# Havashenasi.net
KiCad netlist of a schematic drawn in Altium Designer
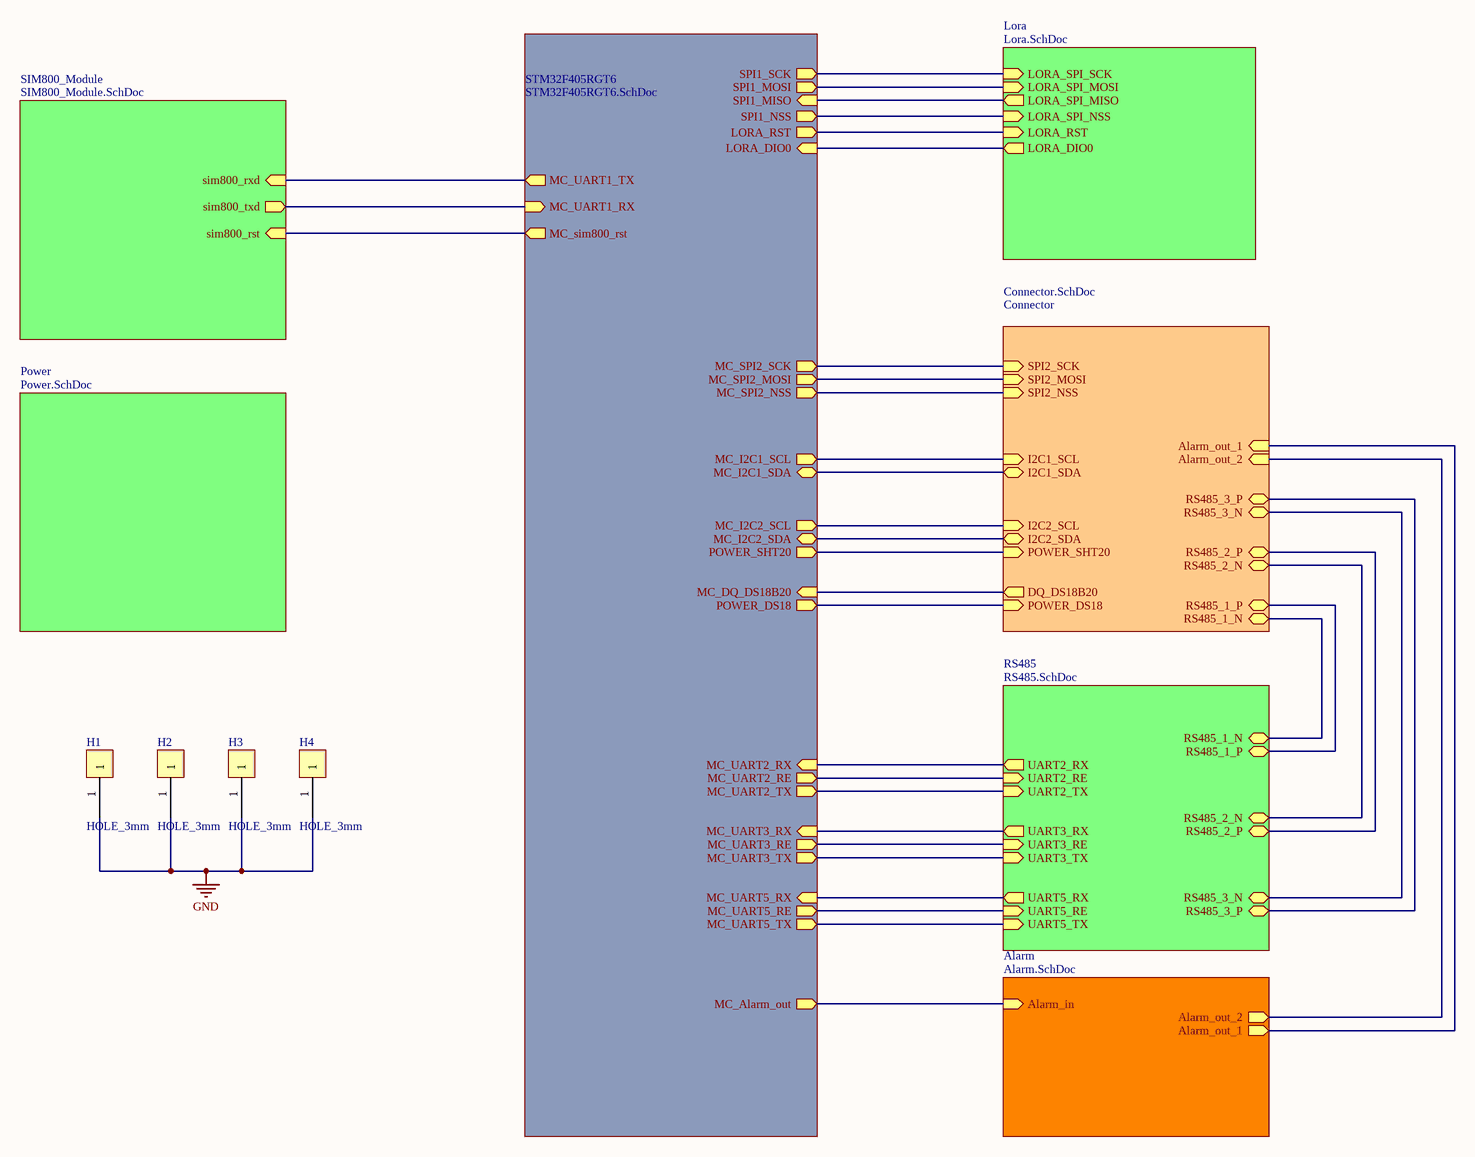
[diagram p0: Havashenasi.SchDoc]

(export (version "E")
  (design (tool "Eeschema 10.0.6"))
  (components
    (comp (ref "H1") (value "HOLE_3mm") (footprint "Hole_3mm") (libsource (lib "AfraLIB") (part "HOLE_3mm")))
    (comp (ref "H2") (value "HOLE_3mm") (footprint "Hole_3mm") (libsource (lib "AfraLIB") (part "HOLE_3mm")))
    (comp (ref "H3") (value "HOLE_3mm") (footprint "Hole_3mm") (libsource (lib "AfraLIB") (part "HOLE_3mm")))
    (comp (ref "H4") (value "HOLE_3mm") (footprint "Hole_3mm") (libsource (lib "AfraLIB") (part "HOLE_3mm")))
  )
  (nets
    (net (code "38") (name "GND") (class "Default")
      (node (ref "H1") (pin "1") (pinfunction "1_1") (pintype "passive"))
      (node (ref "H2") (pin "1") (pinfunction "1_1") (pintype "passive"))
      (node (ref "H3") (pin "1") (pinfunction "1_1") (pintype "passive"))
      (node (ref "H4") (pin "1") (pinfunction "1_1") (pintype "passive"))
    )
  )
)
